# cam_new.net
KiCad netlist of a schematic drawn in EAGLE
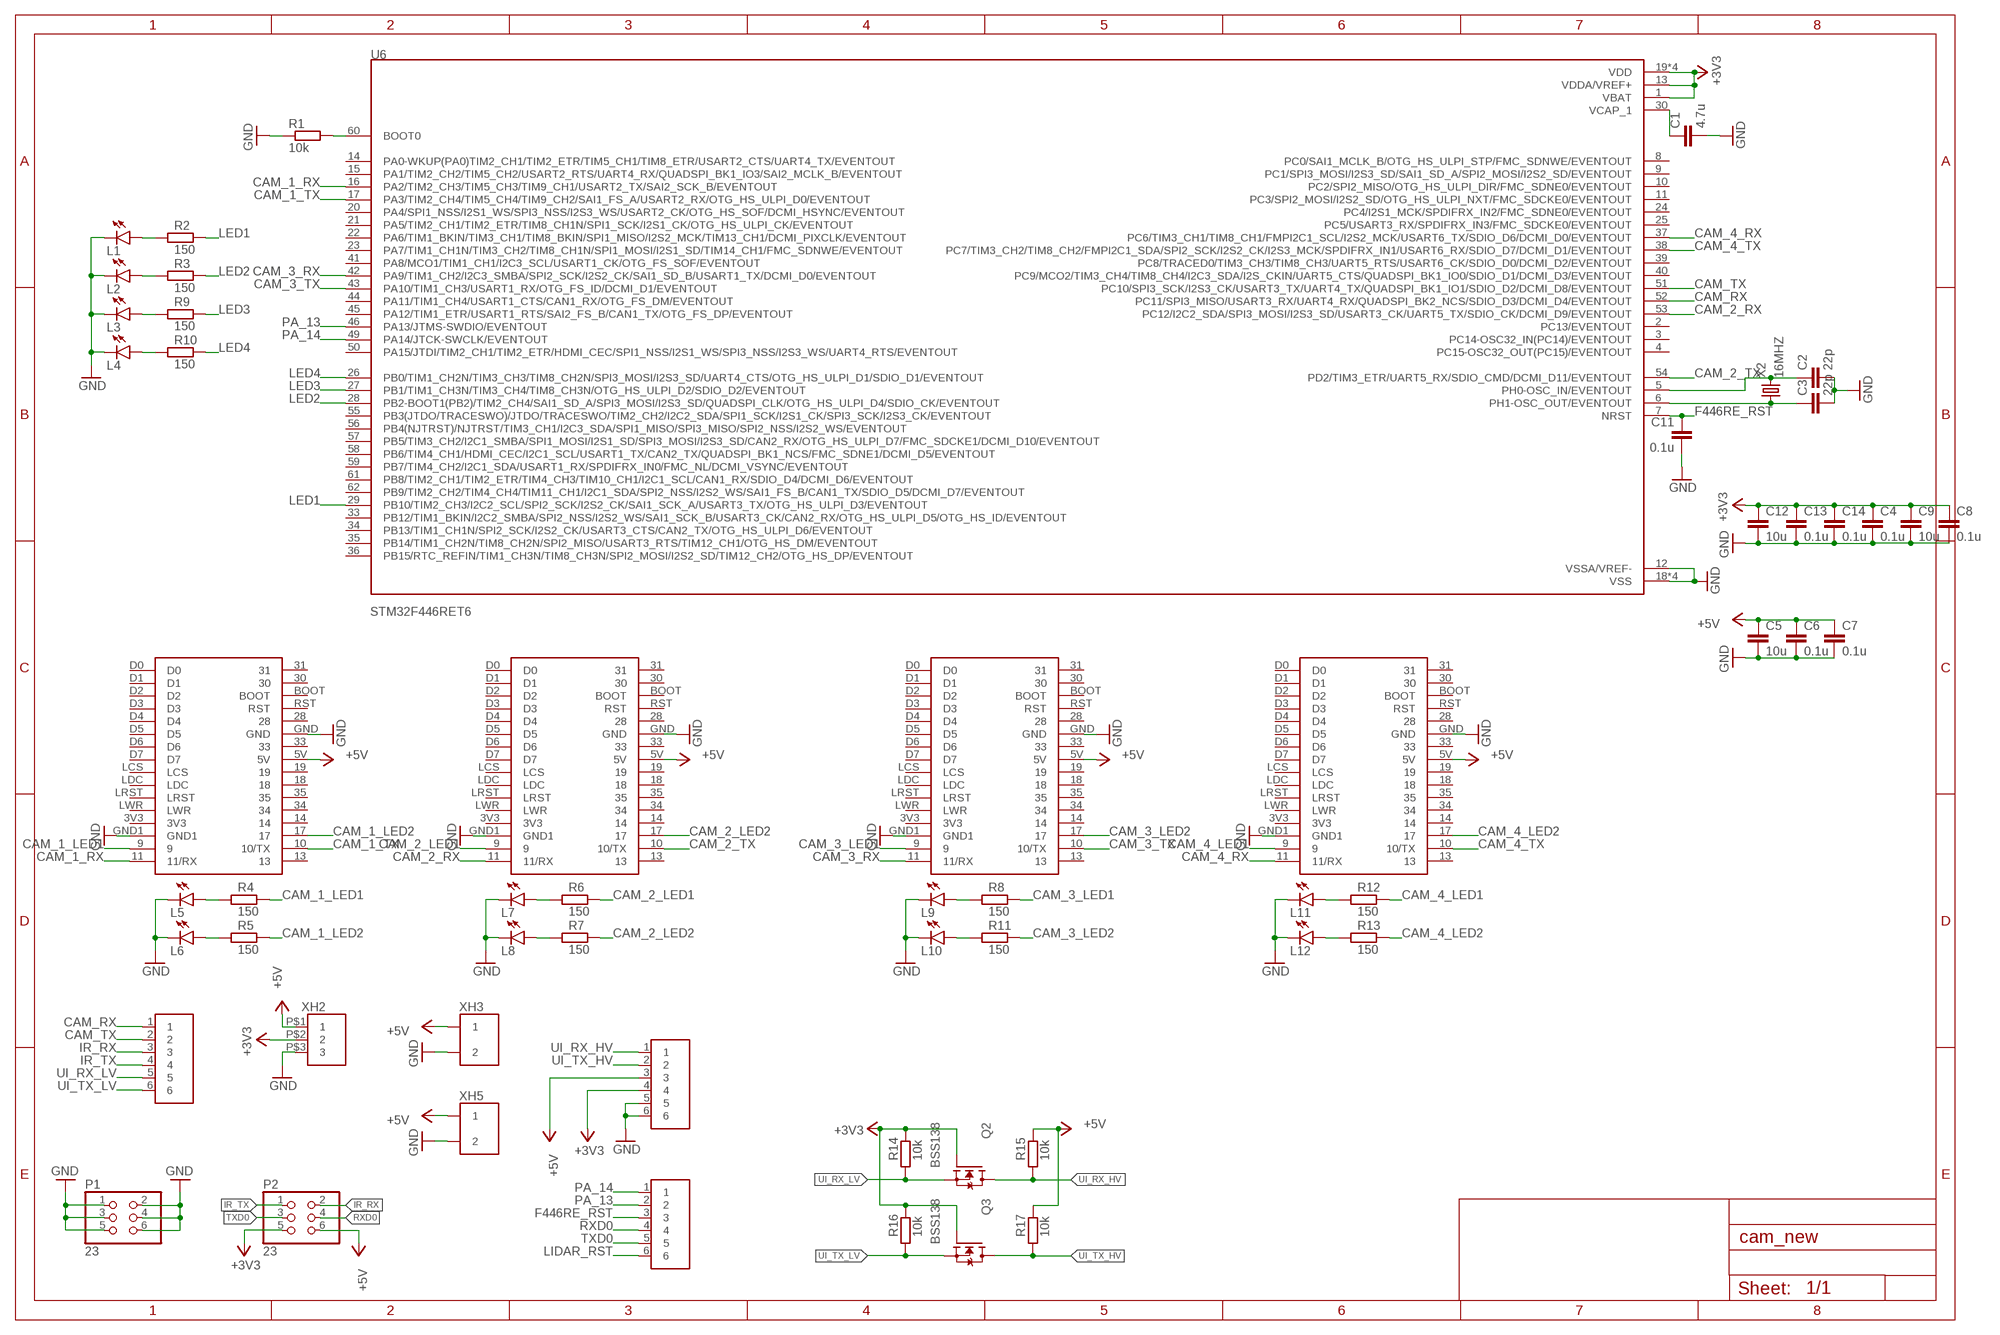
[diagram p0: schematic, sheet 1]

(export (version "E")
  (design (tool "Eeschema 10.0.6"))
  (components
    (comp (ref "C1")
      (value "4.7u")
      (footprint "eagle-import:C0603")
      (libsource (lib "eagle-import") (part "C-EUC0603"))
    )
    (comp (ref "C2")
      (value "22p")
      (footprint "eagle-import:C0603")
      (libsource (lib "eagle-import") (part "C-EUC0603"))
    )
    (comp (ref "C3")
      (value "22p")
      (footprint "eagle-import:C0603")
      (libsource (lib "eagle-import") (part "C-EUC0603"))
    )
    (comp (ref "C4")
      (value "0.1u")
      (footprint "eagle-import:C0603")
      (libsource (lib "eagle-import") (part "C-EUC0603"))
    )
    (comp (ref "C5")
      (value "10u")
      (footprint "eagle-import:C0805")
      (libsource (lib "eagle-import") (part "C-EUC0805"))
    )
    (comp (ref "C6")
      (value "0.1u")
      (footprint "eagle-import:C0603")
      (libsource (lib "eagle-import") (part "C-EUC0603"))
    )
    (comp (ref "C7")
      (value "0.1u")
      (footprint "eagle-import:C0603")
      (libsource (lib "eagle-import") (part "C-EUC0603"))
    )
    (comp (ref "C8")
      (value "0.1u")
      (footprint "eagle-import:C0603")
      (libsource (lib "eagle-import") (part "C-EUC0603"))
    )
    (comp (ref "C9")
      (value "10u")
      (footprint "eagle-import:C0805")
      (libsource (lib "eagle-import") (part "C-EUC0805"))
    )
    (comp (ref "C11")
      (value "0.1u")
      (footprint "eagle-import:C0603")
      (libsource (lib "eagle-import") (part "C-EUC0603"))
    )
    (comp (ref "C12")
      (value "10u")
      (footprint "eagle-import:C0805")
      (libsource (lib "eagle-import") (part "C-EUC0805"))
    )
    (comp (ref "C13")
      (value "0.1u")
      (footprint "eagle-import:C0603")
      (libsource (lib "eagle-import") (part "C-EUC0603"))
    )
    (comp (ref "C14")
      (value "0.1u")
      (footprint "eagle-import:C0603")
      (libsource (lib "eagle-import") (part "C-EUC0603"))
    )
    (comp (ref "L1")
      (value "SML-E12P8WT86")
      (footprint "eagle-import:LED_SML-LXFM0603SIC-TR")
      (libsource (lib "eagle-import") (part "SML-E12P8WT86"))
    )
    (comp (ref "L2")
      (value "SML-E12P8WT86")
      (footprint "eagle-import:LED_SML-LXFM0603SIC-TR")
      (libsource (lib "eagle-import") (part "SML-E12P8WT86"))
    )
    (comp (ref "L3")
      (value "SML-E12P8WT86")
      (footprint "eagle-import:LED_SML-LXFM0603SIC-TR")
      (libsource (lib "eagle-import") (part "SML-E12P8WT86"))
    )
    (comp (ref "L4")
      (value "SML-E12P8WT86")
      (footprint "eagle-import:LED_SML-LXFM0603SIC-TR")
      (libsource (lib "eagle-import") (part "SML-E12P8WT86"))
    )
    (comp (ref "L5")
      (value "SML-E12P8WT86")
      (footprint "eagle-import:LED_SML-LXFM0603SIC-TR")
      (libsource (lib "eagle-import") (part "SML-E12P8WT86"))
    )
    (comp (ref "L6")
      (value "SML-E12P8WT86")
      (footprint "eagle-import:LED_SML-LXFM0603SIC-TR")
      (libsource (lib "eagle-import") (part "SML-E12P8WT86"))
    )
    (comp (ref "L7")
      (value "SML-E12P8WT86")
      (footprint "eagle-import:LED_SML-LXFM0603SIC-TR")
      (libsource (lib "eagle-import") (part "SML-E12P8WT86"))
    )
    (comp (ref "L8")
      (value "SML-E12P8WT86")
      (footprint "eagle-import:LED_SML-LXFM0603SIC-TR")
      (libsource (lib "eagle-import") (part "SML-E12P8WT86"))
    )
    (comp (ref "L9")
      (value "SML-E12P8WT86")
      (footprint "eagle-import:LED_SML-LXFM0603SIC-TR")
      (libsource (lib "eagle-import") (part "SML-E12P8WT86"))
    )
    (comp (ref "L10")
      (value "SML-E12P8WT86")
      (footprint "eagle-import:LED_SML-LXFM0603SIC-TR")
      (libsource (lib "eagle-import") (part "SML-E12P8WT86"))
    )
    (comp (ref "L11")
      (value "SML-E12P8WT86")
      (footprint "eagle-import:LED_SML-LXFM0603SIC-TR")
      (libsource (lib "eagle-import") (part "SML-E12P8WT86"))
    )
    (comp (ref "L12")
      (value "SML-E12P8WT86")
      (footprint "eagle-import:LED_SML-LXFM0603SIC-TR")
      (libsource (lib "eagle-import") (part "SML-E12P8WT86"))
    )
    (comp (ref "P1") (value "23") (footprint "eagle-import:2_3") (libsource (lib "eagle-import") (part "23")))
    (comp (ref "P2") (value "23") (footprint "eagle-import:2_3") (libsource (lib "eagle-import") (part "23")))
    (comp (ref "Q2")
      (value "BSS138")
      (footprint "eagle-import:SOT95P240X111-3N")
      (fields (field (name "MF") "onsemi"))
      (libsource (lib "eagle-import") (part "BSS138"))
    )
    (comp (ref "Q3")
      (value "BSS138")
      (footprint "eagle-import:SOT95P240X111-3N")
      (fields (field (name "MF") "onsemi"))
      (libsource (lib "eagle-import") (part "BSS138"))
    )
    (comp (ref "R1")
      (value "10k")
      (footprint "eagle-import:R0603")
      (libsource (lib "eagle-import") (part "R-EU_R0603"))
    )
    (comp (ref "R2")
      (value "150")
      (footprint "eagle-import:R0603")
      (libsource (lib "eagle-import") (part "R-EU_R0603"))
    )
    (comp (ref "R3")
      (value "150")
      (footprint "eagle-import:R0603")
      (libsource (lib "eagle-import") (part "R-EU_R0603"))
    )
    (comp (ref "R4")
      (value "150")
      (footprint "eagle-import:R0603")
      (libsource (lib "eagle-import") (part "R-EU_R0603"))
    )
    (comp (ref "R5")
      (value "150")
      (footprint "eagle-import:R0603")
      (libsource (lib "eagle-import") (part "R-EU_R0603"))
    )
    (comp (ref "R6")
      (value "150")
      (footprint "eagle-import:R0603")
      (libsource (lib "eagle-import") (part "R-EU_R0603"))
    )
    (comp (ref "R7")
      (value "150")
      (footprint "eagle-import:R0603")
      (libsource (lib "eagle-import") (part "R-EU_R0603"))
    )
    (comp (ref "R8")
      (value "150")
      (footprint "eagle-import:R0603")
      (libsource (lib "eagle-import") (part "R-EU_R0603"))
    )
    (comp (ref "R9")
      (value "150")
      (footprint "eagle-import:R0603")
      (libsource (lib "eagle-import") (part "R-EU_R0603"))
    )
    (comp (ref "R10")
      (value "150")
      (footprint "eagle-import:R0603")
      (libsource (lib "eagle-import") (part "R-EU_R0603"))
    )
    (comp (ref "R11")
      (value "150")
      (footprint "eagle-import:R0603")
      (libsource (lib "eagle-import") (part "R-EU_R0603"))
    )
    (comp (ref "R12")
      (value "150")
      (footprint "eagle-import:R0603")
      (libsource (lib "eagle-import") (part "R-EU_R0603"))
    )
    (comp (ref "R13")
      (value "150")
      (footprint "eagle-import:R0603")
      (libsource (lib "eagle-import") (part "R-EU_R0603"))
    )
    (comp (ref "R14")
      (value "10k")
      (footprint "eagle-import:R0603")
      (libsource (lib "eagle-import") (part "R-EU_R0603"))
    )
    (comp (ref "R15")
      (value "10k")
      (footprint "eagle-import:R0603")
      (libsource (lib "eagle-import") (part "R-EU_R0603"))
    )
    (comp (ref "R16")
      (value "10k")
      (footprint "eagle-import:R0603")
      (libsource (lib "eagle-import") (part "R-EU_R0603"))
    )
    (comp (ref "R17")
      (value "10k")
      (footprint "eagle-import:R0603")
      (libsource (lib "eagle-import") (part "R-EU_R0603"))
    )
    (comp (ref "U1")
      (value "M1N")
      (footprint "eagle-import:M1N")
      (libsource (lib "eagle-import") (part "M1N"))
    )
    (comp (ref "U2")
      (value "M1N")
      (footprint "eagle-import:M1N")
      (libsource (lib "eagle-import") (part "M1N"))
    )
    (comp (ref "U3")
      (value "M1N")
      (footprint "eagle-import:M1N")
      (libsource (lib "eagle-import") (part "M1N"))
    )
    (comp (ref "U4")
      (value "M1N")
      (footprint "eagle-import:M1N")
      (libsource (lib "eagle-import") (part "M1N"))
    )
    (comp (ref "U6")
      (value "STM32F446RET6")
      (footprint "eagle-import:QFP50P1200X1200X160-64N")
      (fields (field (name "MF") "STMicroelectronics"))
      (libsource (lib "eagle-import") (part "STM32F446RET6"))
    )
    (comp (ref "X2")
      (value "16MHZ")
      (footprint "eagle-import:16MHZ")
      (libsource (lib "eagle-import") (part "16MHZ"))
    )
    (comp (ref "XH1") (value "6B") (footprint "eagle-import:6B") (libsource (lib "eagle-import") (part "6B")))
    (comp (ref "XH2") (value "3B") (footprint "eagle-import:3B") (libsource (lib "eagle-import") (part "3B")))
    (comp (ref "XH3") (value "2B") (footprint "eagle-import:2B") (libsource (lib "eagle-import") (part "2B")))
    (comp (ref "XH4") (value "6B") (footprint "eagle-import:6B") (libsource (lib "eagle-import") (part "6B")))
    (comp (ref "XH5") (value "2B") (footprint "eagle-import:2B") (libsource (lib "eagle-import") (part "2B")))
    (comp (ref "XH6") (value "6B") (footprint "eagle-import:6B") (libsource (lib "eagle-import") (part "6B")))
  )
  (nets
    (net (code "1") (name "+3V3") (class "Default")
      (node (ref "C12") (pin "1") (pinfunction "1_1") (pintype "passive"))
      (node (ref "C13") (pin "1") (pinfunction "1_1") (pintype "passive"))
      (node (ref "C14") (pin "1") (pinfunction "1_1") (pintype "passive"))
      (node (ref "C4") (pin "1") (pinfunction "1_1") (pintype "passive"))
      (node (ref "C8") (pin "1") (pinfunction "1_1") (pintype "passive"))
      (node (ref "C9") (pin "1") (pinfunction "1_1") (pintype "passive"))
      (node (ref "P2") (pin "5") (pinfunction "5_5") (pintype "passive"))
      (node (ref "Q2") (pin "1") (pinfunction "G_1") (pintype "passive"))
      (node (ref "Q3") (pin "1") (pinfunction "G_1") (pintype "passive"))
      (node (ref "R14") (pin "2") (pinfunction "2_2") (pintype "passive"))
      (node (ref "R16") (pin "2") (pinfunction "2_2") (pintype "passive"))
      (node (ref "U6") (pin "1") (pinfunction "VBAT_1") (pintype "power_in"))
      (node (ref "U6") (pin "13") (pinfunction "VDDA/VREF+_13") (pintype "power_in"))
      (node (ref "U6") (pin "19") (pinfunction "VDD_19") (pintype "power_in"))
      (node (ref "U6") (pin "32") (pinfunction "VDD_32") (pintype "power_in"))
      (node (ref "U6") (pin "48") (pinfunction "VDD_48") (pintype "power_in"))
      (node (ref "U6") (pin "64") (pinfunction "VDD_64") (pintype "power_in"))
      (node (ref "XH2") (pin "P$2") (pinfunction "2_P$2") (pintype "bidirectional"))
      (node (ref "XH4") (pin "4") (pinfunction "4_4") (pintype "bidirectional"))
    )
    (net (code "2") (name "+5V") (class "Default")
      (node (ref "C5") (pin "1") (pinfunction "1_1") (pintype "passive"))
      (node (ref "C6") (pin "1") (pinfunction "1_1") (pintype "passive"))
      (node (ref "C7") (pin "1") (pinfunction "1_1") (pintype "passive"))
      (node (ref "P2") (pin "6") (pinfunction "6_6") (pintype "passive"))
      (node (ref "R15") (pin "2") (pinfunction "2_2") (pintype "passive"))
      (node (ref "R17") (pin "2") (pinfunction "2_2") (pintype "passive"))
      (node (ref "U1") (pin "5V") (pinfunction "5V_5V") (pintype "bidirectional"))
      (node (ref "U2") (pin "5V") (pinfunction "5V_5V") (pintype "bidirectional"))
      (node (ref "U3") (pin "5V") (pinfunction "5V_5V") (pintype "bidirectional"))
      (node (ref "U4") (pin "5V") (pinfunction "5V_5V") (pintype "bidirectional"))
      (node (ref "XH2") (pin "P$1") (pinfunction "1_P$1") (pintype "bidirectional"))
      (node (ref "XH3") (pin "P$1") (pinfunction "1_P$1") (pintype "bidirectional"))
      (node (ref "XH4") (pin "3") (pinfunction "3_3") (pintype "bidirectional"))
      (node (ref "XH5") (pin "P$1") (pinfunction "1_P$1") (pintype "bidirectional"))
    )
    (net (code "3") (name "/CAM_1_LED1") (class "Default")
      (node (ref "R4") (pin "2") (pinfunction "2_2") (pintype "passive"))
      (node (ref "U1") (pin "9") (pinfunction "9_9") (pintype "bidirectional"))
    )
    (net (code "4") (name "/CAM_1_LED2") (class "Default")
      (node (ref "R5") (pin "2") (pinfunction "2_2") (pintype "passive"))
      (node (ref "U1") (pin "17") (pinfunction "17_17") (pintype "bidirectional"))
    )
    (net (code "5") (name "/CAM_1_RX") (class "Default")
      (node (ref "U1") (pin "11") (pinfunction "11/RX_11") (pintype "bidirectional"))
      (node (ref "U6") (pin "16") (pinfunction "PA2/TIM2_CH3/TIM5_CH3/TIM9_CH1/USART2_TX/SAI2_SCK_B/EVENTOUT_16") (pintype "bidirectional"))
    )
    (net (code "6") (name "/CAM_1_TX") (class "Default")
      (node (ref "U1") (pin "10") (pinfunction "10/TX_10") (pintype "bidirectional"))
      (node (ref "U6") (pin "17") (pinfunction "PA3/TIM2_CH4/TIM5_CH4/TIM9_CH2/SAI1_FS_A/USART2_RX/OTG_HS_ULPI_D0/EVENTOUT_17") (pintype "bidirectional"))
    )
    (net (code "7") (name "/CAM_2_LED1") (class "Default")
      (node (ref "R6") (pin "2") (pinfunction "2_2") (pintype "passive"))
      (node (ref "U2") (pin "9") (pinfunction "9_9") (pintype "bidirectional"))
    )
    (net (code "8") (name "/CAM_2_LED2") (class "Default")
      (node (ref "R7") (pin "2") (pinfunction "2_2") (pintype "passive"))
      (node (ref "U2") (pin "17") (pinfunction "17_17") (pintype "bidirectional"))
    )
    (net (code "9") (name "/CAM_2_RX") (class "Default")
      (node (ref "U2") (pin "11") (pinfunction "11/RX_11") (pintype "bidirectional"))
      (node (ref "U6") (pin "53") (pinfunction "PC12/I2C2_SDA/SPI3_MOSI/I2S3_SD/USART3_CK/UART5_TX/SDIO_CK/DCMI_D9/EVENTOUT_53") (pintype "bidirectional"))
    )
    (net (code "10") (name "/CAM_2_TX") (class "Default")
      (node (ref "U2") (pin "10") (pinfunction "10/TX_10") (pintype "bidirectional"))
      (node (ref "U6") (pin "54") (pinfunction "PD2/TIM3_ETR/UART5_RX/SDIO_CMD/DCMI_D11/EVENTOUT_54") (pintype "bidirectional"))
    )
    (net (code "11") (name "/CAM_3_LED1") (class "Default")
      (node (ref "R8") (pin "2") (pinfunction "2_2") (pintype "passive"))
      (node (ref "U3") (pin "9") (pinfunction "9_9") (pintype "bidirectional"))
    )
    (net (code "12") (name "/CAM_3_LED2") (class "Default")
      (node (ref "R11") (pin "2") (pinfunction "2_2") (pintype "passive"))
      (node (ref "U3") (pin "17") (pinfunction "17_17") (pintype "bidirectional"))
    )
    (net (code "13") (name "/CAM_3_RX") (class "Default")
      (node (ref "U3") (pin "11") (pinfunction "11/RX_11") (pintype "bidirectional"))
      (node (ref "U6") (pin "42") (pinfunction "PA9/TIM1_CH2/I2C3_SMBA/SPI2_SCK/I2S2_CK/SAI1_SD_B/USART1_TX/DCMI_D0/EVENTOUT_42") (pintype "bidirectional"))
    )
    (net (code "14") (name "/CAM_3_TX") (class "Default")
      (node (ref "U3") (pin "10") (pinfunction "10/TX_10") (pintype "bidirectional"))
      (node (ref "U6") (pin "43") (pinfunction "PA10/TIM1_CH3/USART1_RX/OTG_FS_ID/DCMI_D1/EVENTOUT_43") (pintype "bidirectional"))
    )
    (net (code "15") (name "/CAM_4_LED1") (class "Default")
      (node (ref "R12") (pin "2") (pinfunction "2_2") (pintype "passive"))
      (node (ref "U4") (pin "9") (pinfunction "9_9") (pintype "bidirectional"))
    )
    (net (code "16") (name "/CAM_4_LED2") (class "Default")
      (node (ref "R13") (pin "2") (pinfunction "2_2") (pintype "passive"))
      (node (ref "U4") (pin "17") (pinfunction "17_17") (pintype "bidirectional"))
    )
    (net (code "17") (name "/CAM_4_RX") (class "Default")
      (node (ref "U4") (pin "11") (pinfunction "11/RX_11") (pintype "bidirectional"))
      (node (ref "U6") (pin "37") (pinfunction "PC6/TIM3_CH1/TIM8_CH1/FMPI2C1_SCL/I2S2_MCK/USART6_TX/SDIO_D6/DCMI_D0/EVENTOUT_37") (pintype "bidirectional"))
    )
    (net (code "18") (name "/CAM_4_TX") (class "Default")
      (node (ref "U4") (pin "10") (pinfunction "10/TX_10") (pintype "bidirectional"))
      (node (ref "U6") (pin "38") (pinfunction "PC7/TIM3_CH2/TIM8_CH2/FMPI2C1_SDA/SPI2_SCK/I2S2_CK/I2S3_MCK/SPDIFRX_IN1/USART6_RX/SDIO_D7/DCMI_D1/EVENTOUT_38") (pintype "bidirectional"))
    )
    (net (code "19") (name "/CAM_RX") (class "Default")
      (node (ref "U6") (pin "52") (pinfunction "PC11/SPI3_MISO/USART3_RX/UART4_RX/QUADSPI_BK2_NCS/SDIO_D3/DCMI_D4/EVENTOUT_52") (pintype "bidirectional"))
      (node (ref "XH1") (pin "1") (pinfunction "1_1") (pintype "bidirectional"))
    )
    (net (code "20") (name "/CAM_TX") (class "Default")
      (node (ref "U6") (pin "51") (pinfunction "PC10/SPI3_SCK/I2S3_CK/USART3_TX/UART4_TX/QUADSPI_BK1_IO1/SDIO_D2/DCMI_D8/EVENTOUT_51") (pintype "bidirectional"))
      (node (ref "XH1") (pin "2") (pinfunction "2_2") (pintype "bidirectional"))
    )
    (net (code "21") (name "/F446RE_RST") (class "Default")
      (node (ref "C11") (pin "1") (pinfunction "1_1") (pintype "passive"))
      (node (ref "U6") (pin "7") (pinfunction "NRST_7") (pintype "bidirectional"))
      (node (ref "XH6") (pin "3") (pinfunction "3_3") (pintype "bidirectional"))
    )
    (net (code "22") (name "/LED1") (class "Default")
      (node (ref "R2") (pin "2") (pinfunction "2_2") (pintype "passive"))
      (node (ref "U6") (pin "29") (pinfunction "PB10/TIM2_CH3/I2C2_SCL/SPI2_SCK/I2S2_CK/SAI1_SCK_A/USART3_TX/OTG_HS_ULPI_D3/EVENTOUT_29") (pintype "bidirectional"))
    )
    (net (code "23") (name "/LED2") (class "Default")
      (node (ref "R3") (pin "2") (pinfunction "2_2") (pintype "passive"))
      (node (ref "U6") (pin "28") (pinfunction "PB2-BOOT1(PB2)/TIM2_CH4/SAI1_SD_A/SPI3_MOSI/I2S3_SD/QUADSPI_CLK/OTG_HS_ULPI_D4/SDIO_CK/EVENTOUT_28") (pintype "bidirectional"))
    )
    (net (code "24") (name "/LED3") (class "Default")
      (node (ref "R9") (pin "2") (pinfunction "2_2") (pintype "passive"))
      (node (ref "U6") (pin "27") (pinfunction "PB1/TIM1_CH3N/TIM3_CH4/TIM8_CH3N/OTG_HS_ULPI_D2/SDIO_D2/EVENTOUT_27") (pintype "bidirectional"))
    )
    (net (code "25") (name "/LED4") (class "Default")
      (node (ref "R10") (pin "2") (pinfunction "2_2") (pintype "passive"))
      (node (ref "U6") (pin "26") (pinfunction "PB0/TIM1_CH2N/TIM3_CH3/TIM8_CH2N/SPI3_MOSI/I2S3_SD/UART4_CTS/OTG_HS_ULPI_D1/SDIO_D1/EVENTOUT_26") (pintype "bidirectional"))
    )
    (net (code "26") (name "/LIDAR_RST") (class "Default")
      (node (ref "XH6") (pin "6") (pinfunction "6_6") (pintype "bidirectional"))
    )
    (net (code "27") (name "/PA_13") (class "Default")
      (node (ref "U6") (pin "46") (pinfunction "PA13/JTMS-SWDIO/EVENTOUT_46") (pintype "bidirectional"))
      (node (ref "XH6") (pin "2") (pinfunction "2_2") (pintype "bidirectional"))
    )
    (net (code "28") (name "/PA_14") (class "Default")
      (node (ref "U6") (pin "49") (pinfunction "PA14/JTCK-SWCLK/EVENTOUT_49") (pintype "bidirectional"))
      (node (ref "XH6") (pin "1") (pinfunction "1_1") (pintype "bidirectional"))
    )
    (net (code "29") (name "GND") (class "Default")
      (node (ref "C1") (pin "2") (pinfunction "2_2") (pintype "passive"))
      (node (ref "C11") (pin "2") (pinfunction "2_2") (pintype "passive"))
      (node (ref "C12") (pin "2") (pinfunction "2_2") (pintype "passive"))
      (node (ref "C13") (pin "2") (pinfunction "2_2") (pintype "passive"))
      (node (ref "C14") (pin "2") (pinfunction "2_2") (pintype "passive"))
      (node (ref "C2") (pin "2") (pinfunction "2_2") (pintype "passive"))
      (node (ref "C3") (pin "2") (pinfunction "2_2") (pintype "passive"))
      (node (ref "C4") (pin "2") (pinfunction "2_2") (pintype "passive"))
      (node (ref "C5") (pin "2") (pinfunction "2_2") (pintype "passive"))
      (node (ref "C6") (pin "2") (pinfunction "2_2") (pintype "passive"))
      (node (ref "C7") (pin "2") (pinfunction "2_2") (pintype "passive"))
      (node (ref "C8") (pin "2") (pinfunction "2_2") (pintype "passive"))
      (node (ref "C9") (pin "2") (pinfunction "2_2") (pintype "passive"))
      (node (ref "L1") (pin "C") (pinfunction "C_C") (pintype "passive"))
      (node (ref "L10") (pin "C") (pinfunction "C_C") (pintype "passive"))
      (node (ref "L11") (pin "C") (pinfunction "C_C") (pintype "passive"))
      (node (ref "L12") (pin "C") (pinfunction "C_C") (pintype "passive"))
      (node (ref "L2") (pin "C") (pinfunction "C_C") (pintype "passive"))
      (node (ref "L3") (pin "C") (pinfunction "C_C") (pintype "passive"))
      (node (ref "L4") (pin "C") (pinfunction "C_C") (pintype "passive"))
      (node (ref "L5") (pin "C") (pinfunction "C_C") (pintype "passive"))
      (node (ref "L6") (pin "C") (pinfunction "C_C") (pintype "passive"))
      (node (ref "L7") (pin "C") (pinfunction "C_C") (pintype "passive"))
      (node (ref "L8") (pin "C") (pinfunction "C_C") (pintype "passive"))
      (node (ref "L9") (pin "C") (pinfunction "C_C") (pintype "passive"))
      (node (ref "P1") (pin "1") (pinfunction "1_1") (pintype "passive"))
      (node (ref "P1") (pin "2") (pinfunction "2_2") (pintype "passive"))
      (node (ref "P1") (pin "3") (pinfunction "3_3") (pintype "passive"))
      (node (ref "P1") (pin "4") (pinfunction "4_4") (pintype "passive"))
      (node (ref "P1") (pin "5") (pinfunction "5_5") (pintype "passive"))
      (node (ref "P1") (pin "6") (pinfunction "6_6") (pintype "passive"))
      (node (ref "R1") (pin "1") (pinfunction "1_1") (pintype "passive"))
      (node (ref "U1") (pin "GND") (pinfunction "GND_GND") (pintype "bidirectional"))
      (node (ref "U1") (pin "GND1") (pinfunction "GND1_GND1") (pintype "bidirectional"))
      (node (ref "U2") (pin "GND") (pinfunction "GND_GND") (pintype "bidirectional"))
      (node (ref "U2") (pin "GND1") (pinfunction "GND1_GND1") (pintype "bidirectional"))
      (node (ref "U3") (pin "GND") (pinfunction "GND_GND") (pintype "bidirectional"))
      (node (ref "U3") (pin "GND1") (pinfunction "GND1_GND1") (pintype "bidirectional"))
      (node (ref "U4") (pin "GND") (pinfunction "GND_GND") (pintype "bidirectional"))
      (node (ref "U4") (pin "GND1") (pinfunction "GND1_GND1") (pintype "bidirectional"))
      (node (ref "U6") (pin "12") (pinfunction "VSSA/VREF-_12") (pintype "power_in"))
      (node (ref "U6") (pin "18") (pinfunction "VSS_18") (pintype "power_in"))
      (node (ref "U6") (pin "31") (pinfunction "VSS_31") (pintype "power_in"))
      (node (ref "U6") (pin "47") (pinfunction "VSS_47") (pintype "power_in"))
      (node (ref "U6") (pin "63") (pinfunction "VSS_63") (pintype "power_in"))
      (node (ref "XH2") (pin "P$3") (pinfunction "3_P$3") (pintype "bidirectional"))
      (node (ref "XH3") (pin "P$2") (pinfunction "2_P$2") (pintype "bidirectional"))
      (node (ref "XH4") (pin "5") (pinfunction "5_5") (pintype "bidirectional"))
      (node (ref "XH4") (pin "6") (pinfunction "6_6") (pintype "bidirectional"))
      (node (ref "XH5") (pin "P$2") (pinfunction "2_P$2") (pintype "bidirectional"))
    )
    (net (code "30") (name "IR_RX") (class "Default")
      (node (ref "P2") (pin "2") (pinfunction "2_2") (pintype "passive"))
      (node (ref "XH1") (pin "3") (pinfunction "3_3") (pintype "bidirectional"))
    )
    (net (code "31") (name "IR_TX") (class "Default")
      (node (ref "P2") (pin "1") (pinfunction "1_1") (pintype "passive"))
      (node (ref "XH1") (pin "4") (pinfunction "4_4") (pintype "bidirectional"))
    )
    (net (code "32") (name "Net-(L1-PadA)") (class "Default")
      (node (ref "L1") (pin "A") (pinfunction "A_A") (pintype "passive"))
      (node (ref "R2") (pin "1") (pinfunction "1_1") (pintype "passive"))
    )
    (net (code "33") (name "Net-(L2-PadA)") (class "Default")
      (node (ref "L2") (pin "A") (pinfunction "A_A") (pintype "passive"))
      (node (ref "R3") (pin "1") (pinfunction "1_1") (pintype "passive"))
    )
    (net (code "34") (name "Net-(L3-PadA)") (class "Default")
      (node (ref "L3") (pin "A") (pinfunction "A_A") (pintype "passive"))
      (node (ref "R9") (pin "1") (pinfunction "1_1") (pintype "passive"))
    )
    (net (code "35") (name "Net-(L4-PadA)") (class "Default")
      (node (ref "L4") (pin "A") (pinfunction "A_A") (pintype "passive"))
      (node (ref "R10") (pin "1") (pinfunction "1_1") (pintype "passive"))
    )
    (net (code "36") (name "Net-(L5-PadA)") (class "Default")
      (node (ref "L5") (pin "A") (pinfunction "A_A") (pintype "passive"))
      (node (ref "R4") (pin "1") (pinfunction "1_1") (pintype "passive"))
    )
    (net (code "37") (name "Net-(L6-PadA)") (class "Default")
      (node (ref "L6") (pin "A") (pinfunction "A_A") (pintype "passive"))
      (node (ref "R5") (pin "1") (pinfunction "1_1") (pintype "passive"))
    )
    (net (code "38") (name "Net-(L7-PadA)") (class "Default")
      (node (ref "L7") (pin "A") (pinfunction "A_A") (pintype "passive"))
      (node (ref "R6") (pin "1") (pinfunction "1_1") (pintype "passive"))
    )
    (net (code "39") (name "Net-(L8-PadA)") (class "Default")
      (node (ref "L8") (pin "A") (pinfunction "A_A") (pintype "passive"))
      (node (ref "R7") (pin "1") (pinfunction "1_1") (pintype "passive"))
    )
    (net (code "40") (name "Net-(L9-PadA)") (class "Default")
      (node (ref "L9") (pin "A") (pinfunction "A_A") (pintype "passive"))
      (node (ref "R8") (pin "1") (pinfunction "1_1") (pintype "passive"))
    )
    (net (code "41") (name "Net-(L10-PadA)") (class "Default")
      (node (ref "L10") (pin "A") (pinfunction "A_A") (pintype "passive"))
      (node (ref "R11") (pin "1") (pinfunction "1_1") (pintype "passive"))
    )
    (net (code "42") (name "Net-(L11-PadA)") (class "Default")
      (node (ref "L11") (pin "A") (pinfunction "A_A") (pintype "passive"))
      (node (ref "R12") (pin "1") (pinfunction "1_1") (pintype "passive"))
    )
    (net (code "43") (name "Net-(L12-PadA)") (class "Default")
      (node (ref "L12") (pin "A") (pinfunction "A_A") (pintype "passive"))
      (node (ref "R13") (pin "1") (pinfunction "1_1") (pintype "passive"))
    )
    (net (code "44") (name "Net-(U6-BOOT0)") (class "Default")
      (node (ref "R1") (pin "2") (pinfunction "2_2") (pintype "passive"))
      (node (ref "U6") (pin "60") (pinfunction "BOOT0_60") (pintype "input"))
    )
    (net (code "45") (name "Net-(U6-PH0-OSC_IN{slash}EVENTOUT)") (class "Default")
      (node (ref "C2") (pin "1") (pinfunction "1_1") (pintype "passive"))
      (node (ref "U6") (pin "5") (pinfunction "PH0-OSC_IN/EVENTOUT_5") (pintype "bidirectional"))
      (node (ref "X2") (pin "P$2") (pinfunction "2_P$2") (pintype "passive"))
    )
    (net (code "46") (name "Net-(U6-PH1-OSC_OUT{slash}EVENTOUT)") (class "Default")
      (node (ref "C3") (pin "1") (pinfunction "1_1") (pintype "passive"))
      (node (ref "U6") (pin "6") (pinfunction "PH1-OSC_OUT/EVENTOUT_6") (pintype "bidirectional"))
      (node (ref "X2") (pin "P$1") (pinfunction "1_P$1") (pintype "passive"))
    )
    (net (code "47") (name "Net-(U6-VCAP_1)") (class "Default")
      (node (ref "C1") (pin "1") (pinfunction "1_1") (pintype "passive"))
      (node (ref "U6") (pin "30") (pinfunction "VCAP_1_30") (pintype "power_in"))
    )
    (net (code "48") (name "RXD0") (class "Default")
      (node (ref "P2") (pin "4") (pinfunction "4_4") (pintype "passive"))
      (node (ref "XH6") (pin "4") (pinfunction "4_4") (pintype "bidirectional"))
    )
    (net (code "49") (name "TXD0") (class "Default")
      (node (ref "P2") (pin "3") (pinfunction "3_3") (pintype "passive"))
      (node (ref "XH6") (pin "5") (pinfunction "5_5") (pintype "bidirectional"))
    )
    (net (code "50") (name "UI_RX_HV") (class "Default")
      (node (ref "Q2") (pin "3") (pinfunction "D_3") (pintype "passive"))
      (node (ref "R15") (pin "1") (pinfunction "1_1") (pintype "passive"))
      (node (ref "XH4") (pin "1") (pinfunction "1_1") (pintype "bidirectional"))
    )
    (net (code "51") (name "UI_RX_LV") (class "Default")
      (node (ref "Q2") (pin "2") (pinfunction "S_2") (pintype "passive"))
      (node (ref "R14") (pin "1") (pinfunction "1_1") (pintype "passive"))
      (node (ref "XH1") (pin "5") (pinfunction "5_5") (pintype "bidirectional"))
    )
    (net (code "52") (name "UI_TX_HV") (class "Default")
      (node (ref "Q3") (pin "3") (pinfunction "D_3") (pintype "passive"))
      (node (ref "R17") (pin "1") (pinfunction "1_1") (pintype "passive"))
      (node (ref "XH4") (pin "2") (pinfunction "2_2") (pintype "bidirectional"))
    )
    (net (code "53") (name "UI_TX_LV") (class "Default")
      (node (ref "Q3") (pin "2") (pinfunction "S_2") (pintype "passive"))
      (node (ref "R16") (pin "1") (pinfunction "1_1") (pintype "passive"))
      (node (ref "XH1") (pin "6") (pinfunction "6_6") (pintype "bidirectional"))
    )
    (net (code "54") (name "unconnected-(U1-Pad3V3)") (class "Default")
      (node (ref "U1") (pin "3V3") (pinfunction "3V3_3V3") (pintype "bidirectional"))
    )
    (net (code "55") (name "unconnected-(U1-Pad13)") (class "Default")
      (node (ref "U1") (pin "13") (pinfunction "13_13") (pintype "bidirectional"))
    )
    (net (code "56") (name "unconnected-(U1-Pad14)") (class "Default")
      (node (ref "U1") (pin "14") (pinfunction "14_14") (pintype "bidirectional"))
    )
    (net (code "57") (name "unconnected-(U1-Pad18)") (class "Default")
      (node (ref "U1") (pin "18") (pinfunction "18_18") (pintype "bidirectional"))
    )
    (net (code "58") (name "unconnected-(U1-Pad19)") (class "Default")
      (node (ref "U1") (pin "19") (pinfunction "19_19") (pintype "bidirectional"))
    )
    (net (code "59") (name "unconnected-(U1-Pad28)") (class "Default")
      (node (ref "U1") (pin "28") (pinfunction "28_28") (pintype "bidirectional"))
    )
    (net (code "60") (name "unconnected-(U1-Pad30)") (class "Default")
      (node (ref "U1") (pin "30") (pinfunction "30_30") (pintype "bidirectional"))
    )
    (net (code "61") (name "unconnected-(U1-Pad31)") (class "Default")
      (node (ref "U1") (pin "31") (pinfunction "31_31") (pintype "bidirectional"))
    )
    (net (code "62") (name "unconnected-(U1-Pad33)") (class "Default")
      (node (ref "U1") (pin "33") (pinfunction "33_33") (pintype "bidirectional"))
    )
    (net (code "63") (name "unconnected-(U1-Pad34)") (class "Default")
      (node (ref "U1") (pin "34") (pinfunction "34_34") (pintype "bidirectional"))
    )
    (net (code "64") (name "unconnected-(U1-Pad35)") (class "Default")
      (node (ref "U1") (pin "35") (pinfunction "35_35") (pintype "bidirectional"))
    )
    (net (code "65") (name "unconnected-(U1-PadBOOT)") (class "Default")
      (node (ref "U1") (pin "BOOT") (pinfunction "BOOT_BOOT") (pintype "bidirectional"))
    )
    (net (code "66") (name "unconnected-(U1-PadD0)") (class "Default")
      (node (ref "U1") (pin "D0") (pinfunction "D0_D0") (pintype "bidirectional"))
    )
    (net (code "67") (name "unconnected-(U1-PadD1)") (class "Default")
      (node (ref "U1") (pin "D1") (pinfunction "D1_D1") (pintype "bidirectional"))
    )
    (net (code "68") (name "unconnected-(U1-PadD2)") (class "Default")
      (node (ref "U1") (pin "D2") (pinfunction "D2_D2") (pintype "bidirectional"))
    )
    (net (code "69") (name "unconnected-(U1-PadD3)") (class "Default")
      (node (ref "U1") (pin "D3") (pinfunction "D3_D3") (pintype "bidirectional"))
    )
    (net (code "70") (name "unconnected-(U1-PadD4)") (class "Default")
      (node (ref "U1") (pin "D4") (pinfunction "D4_D4") (pintype "bidirectional"))
    )
    (net (code "71") (name "unconnected-(U1-PadD5)") (class "Default")
      (node (ref "U1") (pin "D5") (pinfunction "D5_D5") (pintype "bidirectional"))
    )
    (net (code "72") (name "unconnected-(U1-PadD6)") (class "Default")
      (node (ref "U1") (pin "D6") (pinfunction "D6_D6") (pintype "bidirectional"))
    )
    (net (code "73") (name "unconnected-(U1-PadD7)") (class "Default")
      (node (ref "U1") (pin "D7") (pinfunction "D7_D7") (pintype "bidirectional"))
    )
    (net (code "74") (name "unconnected-(U1-PadLCS)") (class "Default")
      (node (ref "U1") (pin "LCS") (pinfunction "LCS_LCS") (pintype "bidirectional"))
    )
    (net (code "75") (name "unconnected-(U1-PadLDC)") (class "Default")
      (node (ref "U1") (pin "LDC") (pinfunction "LDC_LDC") (pintype "bidirectional"))
    )
    (net (code "76") (name "unconnected-(U1-PadLRST)") (class "Default")
      (node (ref "U1") (pin "LRST") (pinfunction "LRST_LRST") (pintype "bidirectional"))
    )
    (net (code "77") (name "unconnected-(U1-PadLWR)") (class "Default")
      (node (ref "U1") (pin "LWR") (pinfunction "LWR_LWR") (pintype "bidirectional"))
    )
    (net (code "78") (name "unconnected-(U1-PadRST)") (class "Default")
      (node (ref "U1") (pin "RST") (pinfunction "RST_RST") (pintype "bidirectional"))
    )
    (net (code "79") (name "unconnected-(U2-Pad3V3)") (class "Default")
      (node (ref "U2") (pin "3V3") (pinfunction "3V3_3V3") (pintype "bidirectional"))
    )
    (net (code "80") (name "unconnected-(U2-Pad13)") (class "Default")
      (node (ref "U2") (pin "13") (pinfunction "13_13") (pintype "bidirectional"))
    )
    (net (code "81") (name "unconnected-(U2-Pad14)") (class "Default")
      (node (ref "U2") (pin "14") (pinfunction "14_14") (pintype "bidirectional"))
    )
    (net (code "82") (name "unconnected-(U2-Pad18)") (class "Default")
      (node (ref "U2") (pin "18") (pinfunction "18_18") (pintype "bidirectional"))
    )
    (net (code "83") (name "unconnected-(U2-Pad19)") (class "Default")
      (node (ref "U2") (pin "19") (pinfunction "19_19") (pintype "bidirectional"))
    )
    (net (code "84") (name "unconnected-(U2-Pad28)") (class "Default")
      (node (ref "U2") (pin "28") (pinfunction "28_28") (pintype "bidirectional"))
    )
    (net (code "85") (name "unconnected-(U2-Pad30)") (class "Default")
      (node (ref "U2") (pin "30") (pinfunction "30_30") (pintype "bidirectional"))
    )
    (net (code "86") (name "unconnected-(U2-Pad31)") (class "Default")
      (node (ref "U2") (pin "31") (pinfunction "31_31") (pintype "bidirectional"))
    )
    (net (code "87") (name "unconnected-(U2-Pad33)") (class "Default")
      (node (ref "U2") (pin "33") (pinfunction "33_33") (pintype "bidirectional"))
    )
    (net (code "88") (name "unconnected-(U2-Pad34)") (class "Default")
      (node (ref "U2") (pin "34") (pinfunction "34_34") (pintype "bidirectional"))
    )
    (net (code "89") (name "unconnected-(U2-Pad35)") (class "Default")
      (node (ref "U2") (pin "35") (pinfunction "35_35") (pintype "bidirectional"))
    )
    (net (code "90") (name "unconnected-(U2-PadBOOT)") (class "Default")
      (node (ref "U2") (pin "BOOT") (pinfunction "BOOT_BOOT") (pintype "bidirectional"))
    )
    (net (code "91") (name "unconnected-(U2-PadD0)") (class "Default")
      (node (ref "U2") (pin "D0") (pinfunction "D0_D0") (pintype "bidirectional"))
    )
    (net (code "92") (name "unconnected-(U2-PadD1)") (class "Default")
      (node (ref "U2") (pin "D1") (pinfunction "D1_D1") (pintype "bidirectional"))
    )
    (net (code "93") (name "unconnected-(U2-PadD2)") (class "Default")
      (node (ref "U2") (pin "D2") (pinfunction "D2_D2") (pintype "bidirectional"))
    )
    (net (code "94") (name "unconnected-(U2-PadD3)") (class "Default")
      (node (ref "U2") (pin "D3") (pinfunction "D3_D3") (pintype "bidirectional"))
    )
    (net (code "95") (name "unconnected-(U2-PadD4)") (class "Default")
      (node (ref "U2") (pin "D4") (pinfunction "D4_D4") (pintype "bidirectional"))
    )
    (net (code "96") (name "unconnected-(U2-PadD5)") (class "Default")
      (node (ref "U2") (pin "D5") (pinfunction "D5_D5") (pintype "bidirectional"))
    )
    (net (code "97") (name "unconnected-(U2-PadD6)") (class "Default")
      (node (ref "U2") (pin "D6") (pinfunction "D6_D6") (pintype "bidirectional"))
    )
    (net (code "98") (name "unconnected-(U2-PadD7)") (class "Default")
      (node (ref "U2") (pin "D7") (pinfunction "D7_D7") (pintype "bidirectional"))
    )
    (net (code "99") (name "unconnected-(U2-PadLCS)") (class "Default")
      (node (ref "U2") (pin "LCS") (pinfunction "LCS_LCS") (pintype "bidirectional"))
    )
    (net (code "100") (name "unconnected-(U2-PadLDC)") (class "Default")
      (node (ref "U2") (pin "LDC") (pinfunction "LDC_LDC") (pintype "bidirectional"))
    )
    (net (code "101") (name "unconnected-(U2-PadLRST)") (class "Default")
      (node (ref "U2") (pin "LRST") (pinfunction "LRST_LRST") (pintype "bidirectional"))
    )
    (net (code "102") (name "unconnected-(U2-PadLWR)") (class "Default")
      (node (ref "U2") (pin "LWR") (pinfunction "LWR_LWR") (pintype "bidirectional"))
    )
    (net (code "103") (name "unconnected-(U2-PadRST)") (class "Default")
      (node (ref "U2") (pin "RST") (pinfunction "RST_RST") (pintype "bidirectional"))
    )
    (net (code "104") (name "unconnected-(U3-Pad3V3)") (class "Default")
      (node (ref "U3") (pin "3V3") (pinfunction "3V3_3V3") (pintype "bidirectional"))
    )
    (net (code "105") (name "unconnected-(U3-Pad13)") (class "Default")
      (node (ref "U3") (pin "13") (pinfunction "13_13") (pintype "bidirectional"))
    )
    (net (code "106") (name "unconnected-(U3-Pad14)") (class "Default")
      (node (ref "U3") (pin "14") (pinfunction "14_14") (pintype "bidirectional"))
    )
    (net (code "107") (name "unconnected-(U3-Pad18)") (class "Default")
      (node (ref "U3") (pin "18") (pinfunction "18_18") (pintype "bidirectional"))
    )
    (net (code "108") (name "unconnected-(U3-Pad19)") (class "Default")
      (node (ref "U3") (pin "19") (pinfunction "19_19") (pintype "bidirectional"))
    )
    (net (code "109") (name "unconnected-(U3-Pad28)") (class "Default")
      (node (ref "U3") (pin "28") (pinfunction "28_28") (pintype "bidirectional"))
    )
    (net (code "110") (name "unconnected-(U3-Pad30)") (class "Default")
      (node (ref "U3") (pin "30") (pinfunction "30_30") (pintype "bidirectional"))
    )
    (net (code "111") (name "unconnected-(U3-Pad31)") (class "Default")
      (node (ref "U3") (pin "31") (pinfunction "31_31") (pintype "bidirectional"))
    )
    (net (code "112") (name "unconnected-(U3-Pad33)") (class "Default")
      (node (ref "U3") (pin "33") (pinfunction "33_33") (pintype "bidirectional"))
    )
    (net (code "113") (name "unconnected-(U3-Pad34)") (class "Default")
      (node (ref "U3") (pin "34") (pinfunction "34_34") (pintype "bidirectional"))
    )
    (net (code "114") (name "unconnected-(U3-Pad35)") (class "Default")
      (node (ref "U3") (pin "35") (pinfunction "35_35") (pintype "bidirectional"))
    )
    (net (code "115") (name "unconnected-(U3-PadBOOT)") (class "Default")
      (node (ref "U3") (pin "BOOT") (pinfunction "BOOT_BOOT") (pintype "bidirectional"))
    )
    (net (code "116") (name "unconnected-(U3-PadD0)") (class "Default")
      (node (ref "U3") (pin "D0") (pinfunction "D0_D0") (pintype "bidirectional"))
    )
    (net (code "117") (name "unconnected-(U3-PadD1)") (class "Default")
      (node (ref "U3") (pin "D1") (pinfunction "D1_D1") (pintype "bidirectional"))
    )
    (net (code "118") (name "unconnected-(U3-PadD2)") (class "Default")
      (node (ref "U3") (pin "D2") (pinfunction "D2_D2") (pintype "bidirectional"))
    )
    (net (code "119") (name "unconnected-(U3-PadD3)") (class "Default")
      (node (ref "U3") (pin "D3") (pinfunction "D3_D3") (pintype "bidirectional"))
    )
    (net (code "120") (name "unconnected-(U3-PadD4)") (class "Default")
      (node (ref "U3") (pin "D4") (pinfunction "D4_D4") (pintype "bidirectional"))
    )
    (net (code "121") (name "unconnected-(U3-PadD5)") (class "Default")
      (node (ref "U3") (pin "D5") (pinfunction "D5_D5") (pintype "bidirectional"))
    )
    (net (code "122") (name "unconnected-(U3-PadD6)") (class "Default")
      (node (ref "U3") (pin "D6") (pinfunction "D6_D6") (pintype "bidirectional"))
    )
    (net (code "123") (name "unconnected-(U3-PadD7)") (class "Default")
      (node (ref "U3") (pin "D7") (pinfunction "D7_D7") (pintype "bidirectional"))
    )
    (net (code "124") (name "unconnected-(U3-PadLCS)") (class "Default")
      (node (ref "U3") (pin "LCS") (pinfunction "LCS_LCS") (pintype "bidirectional"))
    )
    (net (code "125") (name "unconnected-(U3-PadLDC)") (class "Default")
      (node (ref "U3") (pin "LDC") (pinfunction "LDC_LDC") (pintype "bidirectional"))
    )
    (net (code "126") (name "unconnected-(U3-PadLRST)") (class "Default")
      (node (ref "U3") (pin "LRST") (pinfunction "LRST_LRST") (pintype "bidirectional"))
    )
    (net (code "127") (name "unconnected-(U3-PadLWR)") (class "Default")
      (node (ref "U3") (pin "LWR") (pinfunction "LWR_LWR") (pintype "bidirectional"))
    )
    (net (code "128") (name "unconnected-(U3-PadRST)") (class "Default")
      (node (ref "U3") (pin "RST") (pinfunction "RST_RST") (pintype "bidirectional"))
    )
    (net (code "129") (name "unconnected-(U4-Pad3V3)") (class "Default")
      (node (ref "U4") (pin "3V3") (pinfunction "3V3_3V3") (pintype "bidirectional"))
    )
    (net (code "130") (name "unconnected-(U4-Pad13)") (class "Default")
      (node (ref "U4") (pin "13") (pinfunction "13_13") (pintype "bidirectional"))
    )
    (net (code "131") (name "unconnected-(U4-Pad14)") (class "Default")
      (node (ref "U4") (pin "14") (pinfunction "14_14") (pintype "bidirectional"))
    )
    (net (code "132") (name "unconnected-(U4-Pad18)") (class "Default")
      (node (ref "U4") (pin "18") (pinfunction "18_18") (pintype "bidirectional"))
    )
    (net (code "133") (name "unconnected-(U4-Pad19)") (class "Default")
      (node (ref "U4") (pin "19") (pinfunction "19_19") (pintype "bidirectional"))
    )
    (net (code "134") (name "unconnected-(U4-Pad28)") (class "Default")
      (node (ref "U4") (pin "28") (pinfunction "28_28") (pintype "bidirectional"))
    )
    (net (code "135") (name "unconnected-(U4-Pad30)") (class "Default")
      (node (ref "U4") (pin "30") (pinfunction "30_30") (pintype "bidirectional"))
    )
    (net (code "136") (name "unconnected-(U4-Pad31)") (class "Default")
      (node (ref "U4") (pin "31") (pinfunction "31_31") (pintype "bidirectional"))
    )
    (net (code "137") (name "unconnected-(U4-Pad33)") (class "Default")
      (node (ref "U4") (pin "33") (pinfunction "33_33") (pintype "bidirectional"))
    )
    (net (code "138") (name "unconnected-(U4-Pad34)") (class "Default")
      (node (ref "U4") (pin "34") (pinfunction "34_34") (pintype "bidirectional"))
    )
    (net (code "139") (name "unconnected-(U4-Pad35)") (class "Default")
      (node (ref "U4") (pin "35") (pinfunction "35_35") (pintype "bidirectional"))
    )
    (net (code "140") (name "unconnected-(U4-PadBOOT)") (class "Default")
      (node (ref "U4") (pin "BOOT") (pinfunction "BOOT_BOOT") (pintype "bidirectional"))
    )
    (net (code "141") (name "unconnected-(U4-PadD0)") (class "Default")
      (node (ref "U4") (pin "D0") (pinfunction "D0_D0") (pintype "bidirectional"))
    )
    (net (code "142") (name "unconnected-(U4-PadD1)") (class "Default")
      (node (ref "U4") (pin "D1") (pinfunction "D1_D1") (pintype "bidirectional"))
    )
    (net (code "143") (name "unconnected-(U4-PadD2)") (class "Default")
      (node (ref "U4") (pin "D2") (pinfunction "D2_D2") (pintype "bidirectional"))
    )
    (net (code "144") (name "unconnected-(U4-PadD3)") (class "Default")
      (node (ref "U4") (pin "D3") (pinfunction "D3_D3") (pintype "bidirectional"))
    )
    (net (code "145") (name "unconnected-(U4-PadD4)") (class "Default")
      (node (ref "U4") (pin "D4") (pinfunction "D4_D4") (pintype "bidirectional"))
    )
    (net (code "146") (name "unconnected-(U4-PadD5)") (class "Default")
      (node (ref "U4") (pin "D5") (pinfunction "D5_D5") (pintype "bidirectional"))
    )
    (net (code "147") (name "unconnected-(U4-PadD6)") (class "Default")
      (node (ref "U4") (pin "D6") (pinfunction "D6_D6") (pintype "bidirectional"))
    )
    (net (code "148") (name "unconnected-(U4-PadD7)") (class "Default")
      (node (ref "U4") (pin "D7") (pinfunction "D7_D7") (pintype "bidirectional"))
    )
    (net (code "149") (name "unconnected-(U4-PadLCS)") (class "Default")
      (node (ref "U4") (pin "LCS") (pinfunction "LCS_LCS") (pintype "bidirectional"))
    )
    (net (code "150") (name "unconnected-(U4-PadLDC)") (class "Default")
      (node (ref "U4") (pin "LDC") (pinfunction "LDC_LDC") (pintype "bidirectional"))
    )
    (net (code "151") (name "unconnected-(U4-PadLRST)") (class "Default")
      (node (ref "U4") (pin "LRST") (pinfunction "LRST_LRST") (pintype "bidirectional"))
    )
    (net (code "152") (name "unconnected-(U4-PadLWR)") (class "Default")
      (node (ref "U4") (pin "LWR") (pinfunction "LWR_LWR") (pintype "bidirectional"))
    )
    (net (code "153") (name "unconnected-(U4-PadRST)") (class "Default")
      (node (ref "U4") (pin "RST") (pinfunction "RST_RST") (pintype "bidirectional"))
    )
    (net (code "154") (name "unconnected-(U6-PA0-WKUP(PA0)TIM2_CH1{slash}TIM2_ETR{slash}TIM5_CH1{slash}TIM8_ETR{slash}USART2_CTS{slash}UART4_TX{slash}EVENTOUT-Pad14)") (class "Default")
      (node (ref "U6") (pin "14") (pinfunction "PA0-WKUP(PA0)TIM2_CH1/TIM2_ETR/TIM5_CH1/TIM8_ETR/USART2_CTS/UART4_TX/EVENTOUT_14") (pintype "bidirectional"))
    )
    (net (code "155") (name "unconnected-(U6-PA1{slash}TIM2_CH2{slash}TIM5_CH2{slash}USART2_RTS{slash}UART4_RX{slash}QUADSPI_BK1_IO3{slash}SAI2_MCLK_B{slash}EVENTOUT-Pad15)") (class "Default")
      (node (ref "U6") (pin "15") (pinfunction "PA1/TIM2_CH2/TIM5_CH2/USART2_RTS/UART4_RX/QUADSPI_BK1_IO3/SAI2_MCLK_B/EVENTOUT_15") (pintype "bidirectional"))
    )
    (net (code "156") (name "unconnected-(U6-PA4{slash}SPI1_NSS{slash}I2S1_WS{slash}SPI3_NSS{slash}I2S3_WS{slash}USART2_CK{slash}OTG_HS_SOF{slash}DCMI_HSYNC{slash}EVENTOUT-Pad20)") (class "Default")
      (node (ref "U6") (pin "20") (pinfunction "PA4/SPI1_NSS/I2S1_WS/SPI3_NSS/I2S3_WS/USART2_CK/OTG_HS_SOF/DCMI_HSYNC/EVENTOUT_20") (pintype "bidirectional"))
    )
    (net (code "157") (name "unconnected-(U6-PA5{slash}TIM2_CH1{slash}TIM2_ETR{slash}TIM8_CH1N{slash}SPI1_SCK{slash}I2S1_CK{slash}OTG_HS_ULPI_CK{slash}EVENTOUT-Pad21)") (class "Default")
      (node (ref "U6") (pin "21") (pinfunction "PA5/TIM2_CH1/TIM2_ETR/TIM8_CH1N/SPI1_SCK/I2S1_CK/OTG_HS_ULPI_CK/EVENTOUT_21") (pintype "bidirectional"))
    )
    (net (code "158") (name "unconnected-(U6-PA6{slash}TIM1_BKIN{slash}TIM3_CH1{slash}TIM8_BKIN{slash}SPI1_MISO{slash}I2S2_MCK{slash}TIM13_CH1{slash}DCMI_PIXCLK{slash}EVENTOUT-Pad22)") (class "Default")
      (node (ref "U6") (pin "22") (pinfunction "PA6/TIM1_BKIN/TIM3_CH1/TIM8_BKIN/SPI1_MISO/I2S2_MCK/TIM13_CH1/DCMI_PIXCLK/EVENTOUT_22") (pintype "bidirectional"))
    )
    (net (code "159") (name "unconnected-(U6-PA7{slash}TIM1_CH1N{slash}TIM3_CH2{slash}TIM8_CH1N{slash}SPI1_MOSI{slash}I2S1_SD{slash}TIM14_CH1{slash}FMC_SDNWE{slash}EVENTOUT-Pad23)") (class "Default")
      (node (ref "U6") (pin "23") (pinfunction "PA7/TIM1_CH1N/TIM3_CH2/TIM8_CH1N/SPI1_MOSI/I2S1_SD/TIM14_CH1/FMC_SDNWE/EVENTOUT_23") (pintype "bidirectional"))
    )
    (net (code "160") (name "unconnected-(U6-PA8{slash}MCO1{slash}TIM1_CH1{slash}I2C3_SCL{slash}USART1_CK{slash}OTG_FS_SOF{slash}EVENTOUT-Pad41)") (class "Default")
      (node (ref "U6") (pin "41") (pinfunction "PA8/MCO1/TIM1_CH1/I2C3_SCL/USART1_CK/OTG_FS_SOF/EVENTOUT_41") (pintype "bidirectional"))
    )
    (net (code "161") (name "unconnected-(U6-PA11{slash}TIM1_CH4{slash}USART1_CTS{slash}CAN1_RX{slash}OTG_FS_DM{slash}EVENTOUT-Pad44)") (class "Default")
      (node (ref "U6") (pin "44") (pinfunction "PA11/TIM1_CH4/USART1_CTS/CAN1_RX/OTG_FS_DM/EVENTOUT_44") (pintype "bidirectional"))
    )
    (net (code "162") (name "unconnected-(U6-PA12{slash}TIM1_ETR{slash}USART1_RTS{slash}SAI2_FS_B{slash}CAN1_TX{slash}OTG_FS_DP{slash}EVENTOUT-Pad45)") (class "Default")
      (node (ref "U6") (pin "45") (pinfunction "PA12/TIM1_ETR/USART1_RTS/SAI2_FS_B/CAN1_TX/OTG_FS_DP/EVENTOUT_45") (pintype "bidirectional"))
    )
    (net (code "163") (name "unconnected-(U6-PA15{slash}JTDI{slash}TIM2_CH1{slash}TIM2_ETR{slash}HDMI_CEC{slash}SPI1_NSS{slash}I2S1_WS{slash}SPI3_NSS{slash}I2S3_WS{slash}UART4_RTS{slash}EVENTOUT-Pad50)") (class "Default")
      (node (ref "U6") (pin "50") (pinfunction "PA15/JTDI/TIM2_CH1/TIM2_ETR/HDMI_CEC/SPI1_NSS/I2S1_WS/SPI3_NSS/I2S3_WS/UART4_RTS/EVENTOUT_50") (pintype "bidirectional"))
    )
    (net (code "164") (name "unconnected-(U6-PB3(JTDO{slash}TRACESWO){slash}JTDO{slash}TRACESWO{slash}TIM2_CH2{slash}I2C2_SDA{slash}SPI1_SCK{slash}I2S1_CK{slash}SPI3_SCK{slash}I2S3_CK{slash}EVENTOUT-Pad55)") (class "Default")
      (node (ref "U6") (pin "55") (pinfunction "PB3(JTDO/TRACESWO)/JTDO/TRACESWO/TIM2_CH2/I2C2_SDA/SPI1_SCK/I2S1_CK/SPI3_SCK/I2S3_CK/EVENTOUT_55") (pintype "bidirectional"))
    )
    (net (code "165") (name "unconnected-(U6-PB4(NJTRST){slash}NJTRST{slash}TIM3_CH1{slash}I2C3_SDA{slash}SPI1_MISO{slash}SPI3_MISO{slash}SPI2_NSS{slash}I2S2_WS{slash}EVENTOUT-Pad56)") (class "Default")
      (node (ref "U6") (pin "56") (pinfunction "PB4(NJTRST)/NJTRST/TIM3_CH1/I2C3_SDA/SPI1_MISO/SPI3_MISO/SPI2_NSS/I2S2_WS/EVENTOUT_56") (pintype "bidirectional"))
    )
    (net (code "166") (name "unconnected-(U6-PB5{slash}TIM3_CH2{slash}I2C1_SMBA{slash}SPI1_MOSI{slash}I2S1_SD{slash}SPI3_MOSI{slash}I2S3_SD{slash}CAN2_RX{slash}OTG_HS_ULPI_D7{slash}FMC_SDCKE1{slash}DCMI_D10{slash}EVENTOUT-Pad57)") (class "Default")
      (node (ref "U6") (pin "57") (pinfunction "PB5/TIM3_CH2/I2C1_SMBA/SPI1_MOSI/I2S1_SD/SPI3_MOSI/I2S3_SD/CAN2_RX/OTG_HS_ULPI_D7/FMC_SDCKE1/DCMI_D10/EVENTOUT_57") (pintype "bidirectional"))
    )
    (net (code "167") (name "unconnected-(U6-PB6{slash}TIM4_CH1{slash}HDMI_CEC{slash}I2C1_SCL{slash}USART1_TX{slash}CAN2_TX{slash}QUADSPI_BK1_NCS{slash}FMC_SDNE1{slash}DCMI_D5{slash}EVENTOUT-Pad58)") (class "Default")
      (node (ref "U6") (pin "58") (pinfunction "PB6/TIM4_CH1/HDMI_CEC/I2C1_SCL/USART1_TX/CAN2_TX/QUADSPI_BK1_NCS/FMC_SDNE1/DCMI_D5/EVENTOUT_58") (pintype "bidirectional"))
    )
    (net (code "168") (name "unconnected-(U6-PB7{slash}TIM4_CH2{slash}I2C1_SDA{slash}USART1_RX{slash}SPDIFRX_IN0{slash}FMC_NL{slash}DCMI_VSYNC{slash}EVENTOUT-Pad59)") (class "Default")
      (node (ref "U6") (pin "59") (pinfunction "PB7/TIM4_CH2/I2C1_SDA/USART1_RX/SPDIFRX_IN0/FMC_NL/DCMI_VSYNC/EVENTOUT_59") (pintype "bidirectional"))
    )
    (net (code "169") (name "unconnected-(U6-PB8{slash}TIM2_CH1{slash}TIM2_ETR{slash}TIM4_CH3{slash}TIM10_CH1{slash}I2C1_SCL{slash}CAN1_RX{slash}SDIO_D4{slash}DCMI_D6{slash}EVENTOUT-Pad61)") (class "Default")
      (node (ref "U6") (pin "61") (pinfunction "PB8/TIM2_CH1/TIM2_ETR/TIM4_CH3/TIM10_CH1/I2C1_SCL/CAN1_RX/SDIO_D4/DCMI_D6/EVENTOUT_61") (pintype "bidirectional"))
    )
    (net (code "170") (name "unconnected-(U6-PB9{slash}TIM2_CH2{slash}TIM4_CH4{slash}TIM11_CH1{slash}I2C1_SDA{slash}SPI2_NSS{slash}I2S2_WS{slash}SAI1_FS_B{slash}CAN1_TX{slash}SDIO_D5{slash}DCMI_D7{slash}EVENTOUT-Pad62)") (class "Default")
      (node (ref "U6") (pin "62") (pinfunction "PB9/TIM2_CH2/TIM4_CH4/TIM11_CH1/I2C1_SDA/SPI2_NSS/I2S2_WS/SAI1_FS_B/CAN1_TX/SDIO_D5/DCMI_D7/EVENTOUT_62") (pintype "bidirectional"))
    )
    (net (code "171") (name "unconnected-(U6-PB12{slash}TIM1_BKIN{slash}I2C2_SMBA{slash}SPI2_NSS{slash}I2S2_WS{slash}SAI1_SCK_B{slash}USART3_CK{slash}CAN2_RX{slash}OTG_HS_ULPI_D5{slash}OTG_HS_ID{slash}EVENTOUT-Pad33)") (class "Default")
      (node (ref "U6") (pin "33") (pinfunction "PB12/TIM1_BKIN/I2C2_SMBA/SPI2_NSS/I2S2_WS/SAI1_SCK_B/USART3_CK/CAN2_RX/OTG_HS_ULPI_D5/OTG_HS_ID/EVENTOUT_33") (pintype "bidirectional"))
    )
    (net (code "172") (name "unconnected-(U6-PB13{slash}TIM1_CH1N{slash}SPI2_SCK{slash}I2S2_CK{slash}USART3_CTS{slash}CAN2_TX{slash}OTG_HS_ULPI_D6{slash}EVENTOUT-Pad34)") (class "Default")
      (node (ref "U6") (pin "34") (pinfunction "PB13/TIM1_CH1N/SPI2_SCK/I2S2_CK/USART3_CTS/CAN2_TX/OTG_HS_ULPI_D6/EVENTOUT_34") (pintype "bidirectional"))
    )
    (net (code "173") (name "unconnected-(U6-PB14{slash}TIM1_CH2N{slash}TIM8_CH2N{slash}SPI2_MISO{slash}USART3_RTS{slash}TIM12_CH1{slash}OTG_HS_DM{slash}EVENTOUT-Pad35)") (class "Default")
      (node (ref "U6") (pin "35") (pinfunction "PB14/TIM1_CH2N/TIM8_CH2N/SPI2_MISO/USART3_RTS/TIM12_CH1/OTG_HS_DM/EVENTOUT_35") (pintype "bidirectional"))
    )
    (net (code "174") (name "unconnected-(U6-PB15{slash}RTC_REFIN{slash}TIM1_CH3N{slash}TIM8_CH3N{slash}SPI2_MOSI{slash}I2S2_SD{slash}TIM12_CH2{slash}OTG_HS_DP{slash}EVENTOUT-Pad36)") (class "Default")
      (node (ref "U6") (pin "36") (pinfunction "PB15/RTC_REFIN/TIM1_CH3N/TIM8_CH3N/SPI2_MOSI/I2S2_SD/TIM12_CH2/OTG_HS_DP/EVENTOUT_36") (pintype "bidirectional"))
    )
    (net (code "175") (name "unconnected-(U6-PC0{slash}SAI1_MCLK_B{slash}OTG_HS_ULPI_STP{slash}FMC_SDNWE{slash}EVENTOUT-Pad8)") (class "Default")
      (node (ref "U6") (pin "8") (pinfunction "PC0/SAI1_MCLK_B/OTG_HS_ULPI_STP/FMC_SDNWE/EVENTOUT_8") (pintype "bidirectional"))
    )
    (net (code "176") (name "unconnected-(U6-PC1{slash}SPI3_MOSI{slash}I2S3_SD{slash}SAI1_SD_A{slash}SPI2_MOSI{slash}I2S2_SD{slash}EVENTOUT-Pad9)") (class "Default")
      (node (ref "U6") (pin "9") (pinfunction "PC1/SPI3_MOSI/I2S3_SD/SAI1_SD_A/SPI2_MOSI/I2S2_SD/EVENTOUT_9") (pintype "bidirectional"))
    )
    (net (code "177") (name "unconnected-(U6-PC2{slash}SPI2_MISO{slash}OTG_HS_ULPI_DIR{slash}FMC_SDNE0{slash}EVENTOUT-Pad10)") (class "Default")
      (node (ref "U6") (pin "10") (pinfunction "PC2/SPI2_MISO/OTG_HS_ULPI_DIR/FMC_SDNE0/EVENTOUT_10") (pintype "bidirectional"))
    )
    (net (code "178") (name "unconnected-(U6-PC3{slash}SPI2_MOSI{slash}I2S2_SD{slash}OTG_HS_ULPI_NXT{slash}FMC_SDCKE0{slash}EVENTOUT-Pad11)") (class "Default")
      (node (ref "U6") (pin "11") (pinfunction "PC3/SPI2_MOSI/I2S2_SD/OTG_HS_ULPI_NXT/FMC_SDCKE0/EVENTOUT_11") (pintype "bidirectional"))
    )
    (net (code "179") (name "unconnected-(U6-PC4{slash}I2S1_MCK{slash}SPDIFRX_IN2{slash}FMC_SDNE0{slash}EVENTOUT-Pad24)") (class "Default")
      (node (ref "U6") (pin "24") (pinfunction "PC4/I2S1_MCK/SPDIFRX_IN2/FMC_SDNE0/EVENTOUT_24") (pintype "bidirectional"))
    )
    (net (code "180") (name "unconnected-(U6-PC5{slash}USART3_RX{slash}SPDIFRX_IN3{slash}FMC_SDCKE0{slash}EVENTOUT-Pad25)") (class "Default")
      (node (ref "U6") (pin "25") (pinfunction "PC5/USART3_RX/SPDIFRX_IN3/FMC_SDCKE0/EVENTOUT_25") (pintype "bidirectional"))
    )
    (net (code "181") (name "unconnected-(U6-PC8{slash}TRACED0{slash}TIM3_CH3{slash}TIM8_CH3{slash}UART5_RTS{slash}USART6_CK{slash}SDIO_D0{slash}DCMI_D2{slash}EVENTOUT-Pad39)") (class "Default")
      (node (ref "U6") (pin "39") (pinfunction "PC8/TRACED0/TIM3_CH3/TIM8_CH3/UART5_RTS/USART6_CK/SDIO_D0/DCMI_D2/EVENTOUT_39") (pintype "bidirectional"))
    )
    (net (code "182") (name "unconnected-(U6-PC9{slash}MCO2{slash}TIM3_CH4{slash}TIM8_CH4{slash}I2C3_SDA{slash}I2S_CKIN{slash}UART5_CTS{slash}QUADSPI_BK1_IO0{slash}SDIO_D1{slash}DCMI_D3{slash}EVENTOUT-Pad40)") (class "Default")
      (node (ref "U6") (pin "40") (pinfunction "PC9/MCO2/TIM3_CH4/TIM8_CH4/I2C3_SDA/I2S_CKIN/UART5_CTS/QUADSPI_BK1_IO0/SDIO_D1/DCMI_D3/EVENTOUT_40") (pintype "bidirectional"))
    )
    (net (code "183") (name "unconnected-(U6-PC13{slash}EVENTOUT-Pad2)") (class "Default")
      (node (ref "U6") (pin "2") (pinfunction "PC13/EVENTOUT_2") (pintype "bidirectional"))
    )
    (net (code "184") (name "unconnected-(U6-PC14-OSC32_IN(PC14){slash}EVENTOUT-Pad3)") (class "Default")
      (node (ref "U6") (pin "3") (pinfunction "PC14-OSC32_IN(PC14)/EVENTOUT_3") (pintype "bidirectional"))
    )
    (net (code "185") (name "unconnected-(U6-PC15-OSC32_OUT(PC15){slash}EVENTOUT-Pad4)") (class "Default")
      (node (ref "U6") (pin "4") (pinfunction "PC15-OSC32_OUT(PC15)/EVENTOUT_4") (pintype "bidirectional"))
    )
  )
)
